# M161C.net
KiCad netlist of a schematic drawn in EAGLE
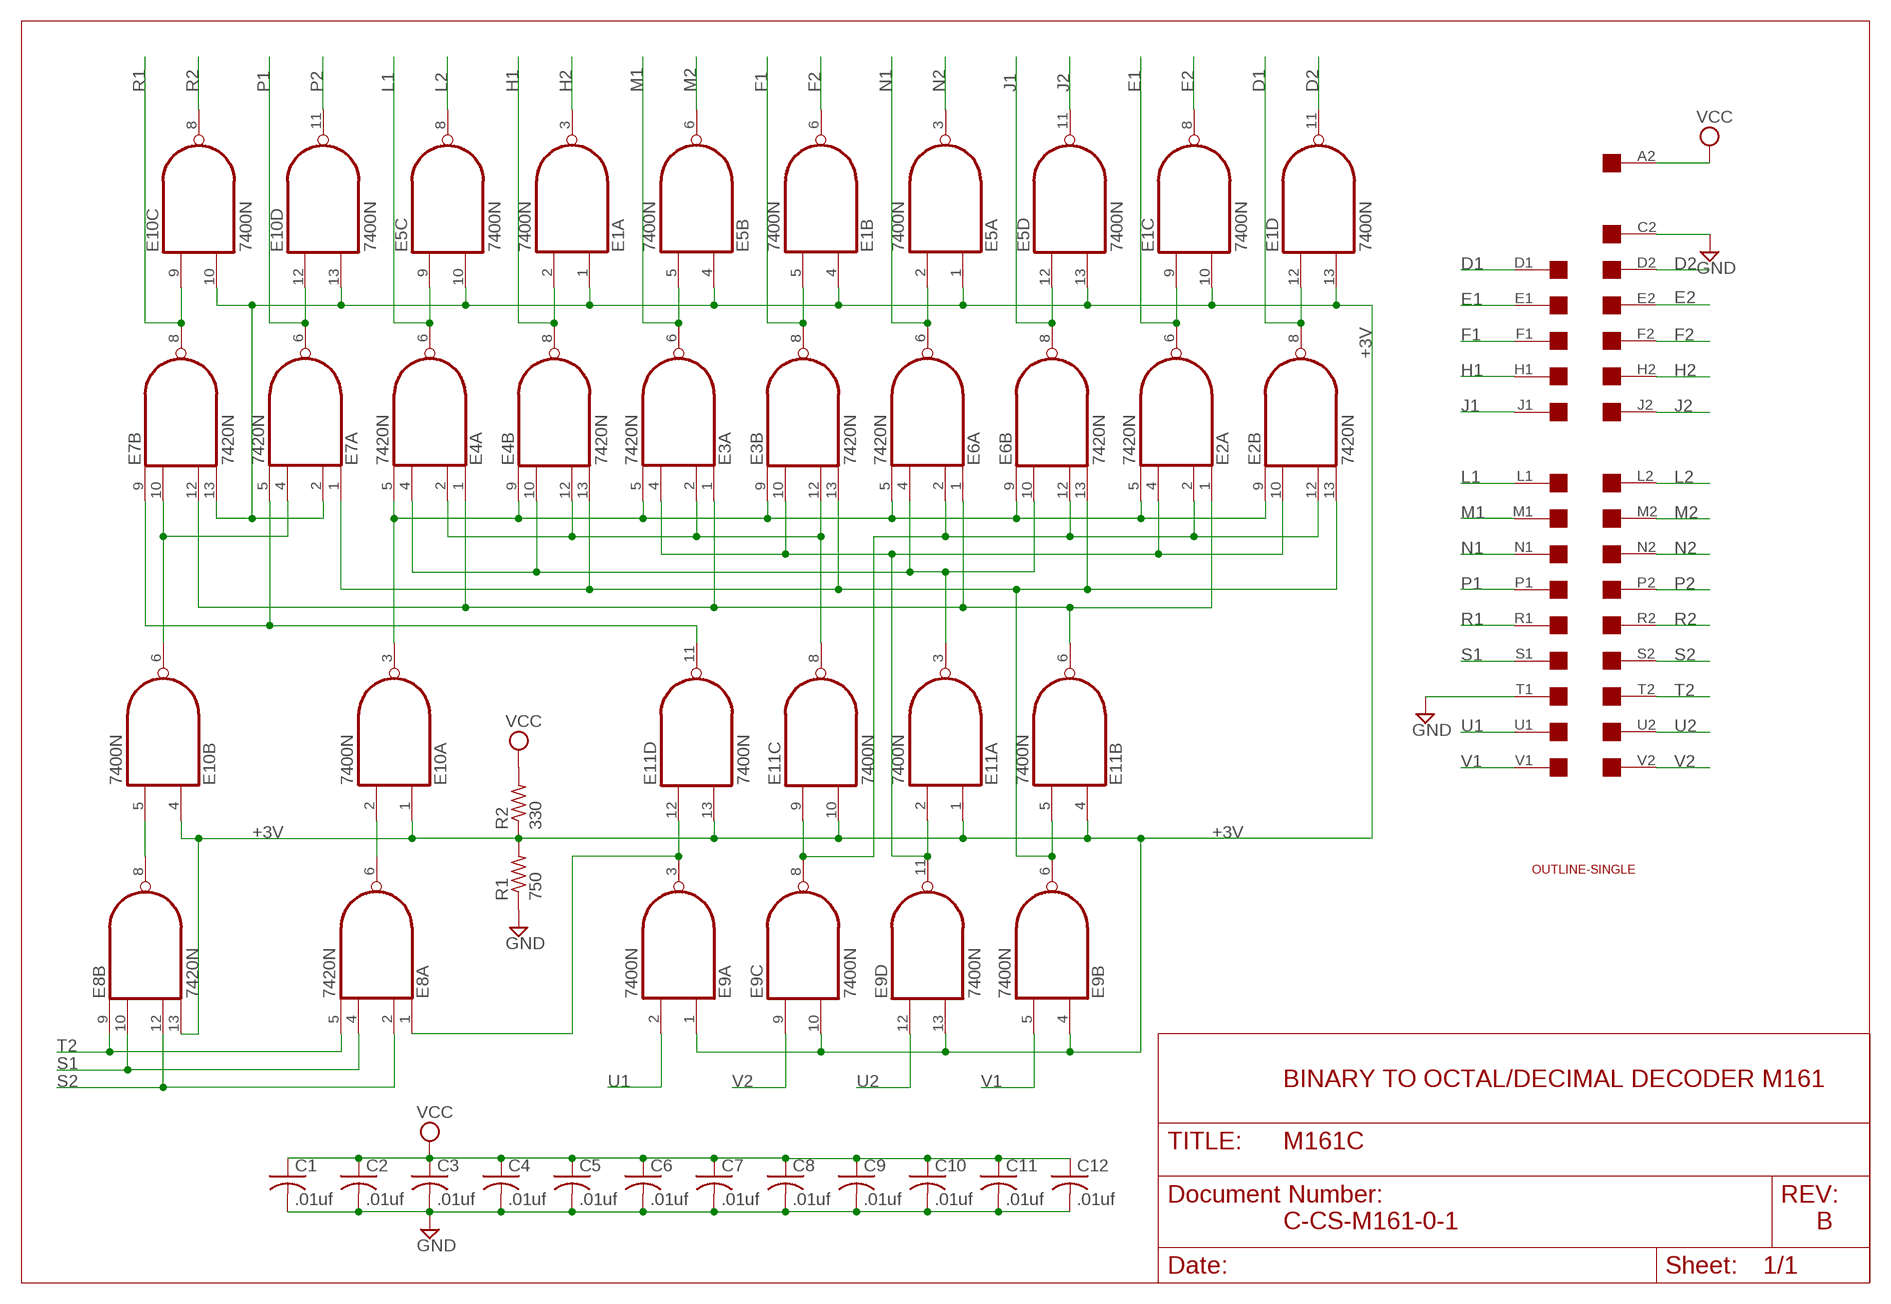
[diagram p0: schematic, sheet 1]

(export (version "E")
  (design (tool "Eeschema 10.0.6"))
  (components
    (comp (ref "C1")
      (value ".01uf")
      (footprint "eagle-import:C050-025X075")
      (libsource (lib "eagle-import") (part "C-US050-025X075"))
    )
    (comp (ref "C2")
      (value ".01uf")
      (footprint "eagle-import:C050-025X075")
      (libsource (lib "eagle-import") (part "C-US050-025X075"))
    )
    (comp (ref "C3")
      (value ".01uf")
      (footprint "eagle-import:C050-025X075")
      (libsource (lib "eagle-import") (part "C-US050-025X075"))
    )
    (comp (ref "C4")
      (value ".01uf")
      (footprint "eagle-import:C050-025X075")
      (libsource (lib "eagle-import") (part "C-US050-025X075"))
    )
    (comp (ref "C5")
      (value ".01uf")
      (footprint "eagle-import:C050-025X075")
      (libsource (lib "eagle-import") (part "C-US050-025X075"))
    )
    (comp (ref "C6")
      (value ".01uf")
      (footprint "eagle-import:C050-025X075")
      (libsource (lib "eagle-import") (part "C-US050-025X075"))
    )
    (comp (ref "C7")
      (value ".01uf")
      (footprint "eagle-import:C050-025X075")
      (libsource (lib "eagle-import") (part "C-US050-025X075"))
    )
    (comp (ref "C8")
      (value ".01uf")
      (footprint "eagle-import:C050-025X075")
      (libsource (lib "eagle-import") (part "C-US050-025X075"))
    )
    (comp (ref "C9")
      (value ".01uf")
      (footprint "eagle-import:C050-025X075")
      (libsource (lib "eagle-import") (part "C-US050-025X075"))
    )
    (comp (ref "C10")
      (value ".01uf")
      (footprint "eagle-import:C050-025X075")
      (libsource (lib "eagle-import") (part "C-US050-025X075"))
    )
    (comp (ref "C11")
      (value ".01uf")
      (footprint "eagle-import:C050-025X075")
      (libsource (lib "eagle-import") (part "C-US050-025X075"))
    )
    (comp (ref "C12")
      (value ".01uf")
      (footprint "eagle-import:C050-025X075")
      (libsource (lib "eagle-import") (part "C-US050-025X075"))
    )
    (comp (ref "E1")
      (value "7400N")
      (footprint "eagle-import:DIL14")
      (libsource (lib "eagle-import") (part "7400N"))
    )
    (comp (ref "E2")
      (value "7420N")
      (footprint "eagle-import:DIL14")
      (libsource (lib "eagle-import") (part "7420NS"))
    )
    (comp (ref "E3")
      (value "7420N")
      (footprint "eagle-import:DIL14")
      (libsource (lib "eagle-import") (part "7420NS"))
    )
    (comp (ref "E4")
      (value "7420N")
      (footprint "eagle-import:DIL14")
      (libsource (lib "eagle-import") (part "7420NS"))
    )
    (comp (ref "E5")
      (value "7400N")
      (footprint "eagle-import:DIL14")
      (libsource (lib "eagle-import") (part "7400N"))
    )
    (comp (ref "E6")
      (value "7420N")
      (footprint "eagle-import:DIL14")
      (libsource (lib "eagle-import") (part "7420NS"))
    )
    (comp (ref "E7")
      (value "7420N")
      (footprint "eagle-import:DIL14")
      (libsource (lib "eagle-import") (part "7420NS"))
    )
    (comp (ref "E8")
      (value "7420N")
      (footprint "eagle-import:DIL14")
      (libsource (lib "eagle-import") (part "7420NS"))
    )
    (comp (ref "E9")
      (value "7400N")
      (footprint "eagle-import:DIL14")
      (libsource (lib "eagle-import") (part "7400N"))
    )
    (comp (ref "E10")
      (value "7400N")
      (footprint "eagle-import:DIL14")
      (libsource (lib "eagle-import") (part "7400N"))
    )
    (comp (ref "E11")
      (value "7400N")
      (footprint "eagle-import:DIL14")
      (libsource (lib "eagle-import") (part "7400N"))
    )
    (comp (ref "R1")
      (value "750")
      (footprint "eagle-import:0207_10")
      (libsource (lib "eagle-import") (part "R-US_0207/10"))
    )
    (comp (ref "R2")
      (value "330")
      (footprint "eagle-import:0207_10")
      (libsource (lib "eagle-import") (part "R-US_0207/10"))
    )
    (comp (ref "U$1")
      (value "OUTLINE-SINGLE")
      (footprint "eagle-import:SINGLE")
      (libsource (lib "eagle-import") (part "OUTLINE-SINGLE"))
    )
    (comp (ref "U$4")
      (value "SINGLE")
      (footprint "eagle-import:EDGE-CON2")
      (libsource (lib "eagle-import") (part "SINGLE"))
    )
  )
  (nets
    (net (code "1") (name "/+3V") (class "Default")
      (node (ref "E1") (pin "1") (pinfunction "I0_1") (pintype "input"))
      (node (ref "E1") (pin "10") (pinfunction "I1_10") (pintype "input"))
      (node (ref "E1") (pin "13") (pinfunction "I1_13") (pintype "input"))
      (node (ref "E1") (pin "4") (pinfunction "I0_4") (pintype "input"))
      (node (ref "E10") (pin "1") (pinfunction "I0_1") (pintype "input"))
      (node (ref "E10") (pin "10") (pinfunction "I1_10") (pintype "input"))
      (node (ref "E10") (pin "13") (pinfunction "I1_13") (pintype "input"))
      (node (ref "E10") (pin "4") (pinfunction "I0_4") (pintype "input"))
      (node (ref "E11") (pin "1") (pinfunction "I0_1") (pintype "input"))
      (node (ref "E11") (pin "10") (pinfunction "I1_10") (pintype "input"))
      (node (ref "E11") (pin "13") (pinfunction "I1_13") (pintype "input"))
      (node (ref "E11") (pin "4") (pinfunction "I0_4") (pintype "input"))
      (node (ref "E5") (pin "1") (pinfunction "I0_1") (pintype "input"))
      (node (ref "E5") (pin "10") (pinfunction "I1_10") (pintype "input"))
      (node (ref "E5") (pin "13") (pinfunction "I1_13") (pintype "input"))
      (node (ref "E5") (pin "4") (pinfunction "I0_4") (pintype "input"))
      (node (ref "E7") (pin "13") (pinfunction "I3_13") (pintype "input"))
      (node (ref "E7") (pin "2") (pinfunction "I1_2") (pintype "input"))
      (node (ref "E8") (pin "13") (pinfunction "I3_13") (pintype "input"))
      (node (ref "E9") (pin "1") (pinfunction "I0_1") (pintype "input"))
      (node (ref "E9") (pin "10") (pinfunction "I1_10") (pintype "input"))
      (node (ref "E9") (pin "13") (pinfunction "I1_13") (pintype "input"))
      (node (ref "E9") (pin "4") (pinfunction "I0_4") (pintype "input"))
      (node (ref "R1") (pin "2") (pinfunction "2_2") (pintype "passive"))
      (node (ref "R2") (pin "1") (pinfunction "1_1") (pintype "passive"))
    )
    (net (code "2") (name "/D1") (class "Default")
      (node (ref "E1") (pin "12") (pinfunction "I0_12") (pintype "input"))
      (node (ref "E2") (pin "8") (pinfunction "O_8") (pintype "output"))
      (node (ref "U$4") (pin "D1") (pinfunction "1_D1") (pintype "bidirectional"))
    )
    (net (code "3") (name "/D2") (class "Default")
      (node (ref "E1") (pin "11") (pinfunction "O_11") (pintype "output"))
      (node (ref "U$4") (pin "D2") (pinfunction "1_D2") (pintype "bidirectional"))
    )
    (net (code "4") (name "/E1") (class "Default")
      (node (ref "E1") (pin "9") (pinfunction "I0_9") (pintype "input"))
      (node (ref "E2") (pin "6") (pinfunction "O_6") (pintype "output"))
      (node (ref "U$4") (pin "E1") (pinfunction "1_E1") (pintype "bidirectional"))
    )
    (net (code "5") (name "/E2") (class "Default")
      (node (ref "E1") (pin "8") (pinfunction "O_8") (pintype "output"))
      (node (ref "U$4") (pin "E2") (pinfunction "1_E2") (pintype "bidirectional"))
    )
    (net (code "6") (name "/F1") (class "Default")
      (node (ref "E1") (pin "5") (pinfunction "I1_5") (pintype "input"))
      (node (ref "E3") (pin "8") (pinfunction "O_8") (pintype "output"))
      (node (ref "U$4") (pin "F1") (pinfunction "1_F1") (pintype "bidirectional"))
    )
    (net (code "7") (name "/F2") (class "Default")
      (node (ref "E1") (pin "6") (pinfunction "O_6") (pintype "output"))
      (node (ref "U$4") (pin "F2") (pinfunction "1_F2") (pintype "bidirectional"))
    )
    (net (code "8") (name "/H1") (class "Default")
      (node (ref "E1") (pin "2") (pinfunction "I1_2") (pintype "input"))
      (node (ref "E4") (pin "8") (pinfunction "O_8") (pintype "output"))
      (node (ref "U$4") (pin "H1") (pinfunction "1_H1") (pintype "bidirectional"))
    )
    (net (code "9") (name "/H2") (class "Default")
      (node (ref "E1") (pin "3") (pinfunction "O_3") (pintype "output"))
      (node (ref "U$4") (pin "H2") (pinfunction "1_H2") (pintype "bidirectional"))
    )
    (net (code "10") (name "/J1") (class "Default")
      (node (ref "E5") (pin "12") (pinfunction "I0_12") (pintype "input"))
      (node (ref "E6") (pin "8") (pinfunction "O_8") (pintype "output"))
      (node (ref "U$4") (pin "J1") (pinfunction "1_J1") (pintype "bidirectional"))
    )
    (net (code "11") (name "/J2") (class "Default")
      (node (ref "E5") (pin "11") (pinfunction "O_11") (pintype "output"))
      (node (ref "U$4") (pin "J2") (pinfunction "1_J2") (pintype "bidirectional"))
    )
    (net (code "12") (name "/L1") (class "Default")
      (node (ref "E4") (pin "6") (pinfunction "O_6") (pintype "output"))
      (node (ref "E5") (pin "9") (pinfunction "I0_9") (pintype "input"))
      (node (ref "U$4") (pin "L1") (pinfunction "1_L1") (pintype "bidirectional"))
    )
    (net (code "13") (name "/L2") (class "Default")
      (node (ref "E5") (pin "8") (pinfunction "O_8") (pintype "output"))
      (node (ref "U$4") (pin "L2") (pinfunction "1_L2") (pintype "bidirectional"))
    )
    (net (code "14") (name "/M1") (class "Default")
      (node (ref "E3") (pin "6") (pinfunction "O_6") (pintype "output"))
      (node (ref "E5") (pin "5") (pinfunction "I1_5") (pintype "input"))
      (node (ref "U$4") (pin "M1") (pinfunction "1_M1") (pintype "bidirectional"))
    )
    (net (code "15") (name "/M2") (class "Default")
      (node (ref "E5") (pin "6") (pinfunction "O_6") (pintype "output"))
      (node (ref "U$4") (pin "M2") (pinfunction "1_M2") (pintype "bidirectional"))
    )
    (net (code "16") (name "/N1") (class "Default")
      (node (ref "E5") (pin "2") (pinfunction "I1_2") (pintype "input"))
      (node (ref "E6") (pin "6") (pinfunction "O_6") (pintype "output"))
      (node (ref "U$4") (pin "N1") (pinfunction "1_N1") (pintype "bidirectional"))
    )
    (net (code "17") (name "/N2") (class "Default")
      (node (ref "E5") (pin "3") (pinfunction "O_3") (pintype "output"))
      (node (ref "U$4") (pin "N2") (pinfunction "1_N2") (pintype "bidirectional"))
    )
    (net (code "18") (name "/P1") (class "Default")
      (node (ref "E10") (pin "12") (pinfunction "I0_12") (pintype "input"))
      (node (ref "E7") (pin "6") (pinfunction "O_6") (pintype "output"))
      (node (ref "U$4") (pin "P1") (pinfunction "1_P1") (pintype "bidirectional"))
    )
    (net (code "19") (name "/P2") (class "Default")
      (node (ref "E10") (pin "11") (pinfunction "O_11") (pintype "output"))
      (node (ref "U$4") (pin "P2") (pinfunction "1_P2") (pintype "bidirectional"))
    )
    (net (code "20") (name "/R1") (class "Default")
      (node (ref "E10") (pin "9") (pinfunction "I0_9") (pintype "input"))
      (node (ref "E7") (pin "8") (pinfunction "O_8") (pintype "output"))
      (node (ref "U$4") (pin "R1") (pinfunction "1_R1") (pintype "bidirectional"))
    )
    (net (code "21") (name "/R2") (class "Default")
      (node (ref "E10") (pin "8") (pinfunction "O_8") (pintype "output"))
      (node (ref "U$4") (pin "R2") (pinfunction "1_R2") (pintype "bidirectional"))
    )
    (net (code "22") (name "/S1") (class "Default")
      (node (ref "E8") (pin "10") (pinfunction "I1_10") (pintype "input"))
      (node (ref "E8") (pin "4") (pinfunction "I2_4") (pintype "input"))
      (node (ref "U$4") (pin "S1") (pinfunction "1_S1") (pintype "bidirectional"))
    )
    (net (code "23") (name "/S2") (class "Default")
      (node (ref "E8") (pin "12") (pinfunction "I2_12") (pintype "input"))
      (node (ref "E8") (pin "2") (pinfunction "I1_2") (pintype "input"))
      (node (ref "U$4") (pin "S2") (pinfunction "1_S2") (pintype "bidirectional"))
    )
    (net (code "24") (name "/T2") (class "Default")
      (node (ref "E8") (pin "5") (pinfunction "I3_5") (pintype "input"))
      (node (ref "E8") (pin "9") (pinfunction "I0_9") (pintype "input"))
      (node (ref "U$4") (pin "T2") (pinfunction "1_T2") (pintype "bidirectional"))
    )
    (net (code "25") (name "/U1") (class "Default")
      (node (ref "E9") (pin "2") (pinfunction "I1_2") (pintype "input"))
      (node (ref "U$4") (pin "U1") (pinfunction "1_U1") (pintype "bidirectional"))
    )
    (net (code "26") (name "/U2") (class "Default")
      (node (ref "E9") (pin "12") (pinfunction "I0_12") (pintype "input"))
      (node (ref "U$4") (pin "U2") (pinfunction "1_U2") (pintype "bidirectional"))
    )
    (net (code "27") (name "/V1") (class "Default")
      (node (ref "E9") (pin "5") (pinfunction "I1_5") (pintype "input"))
      (node (ref "U$4") (pin "V1") (pinfunction "1_V1") (pintype "bidirectional"))
    )
    (net (code "28") (name "/V2") (class "Default")
      (node (ref "E9") (pin "9") (pinfunction "I0_9") (pintype "input"))
      (node (ref "U$4") (pin "V2") (pinfunction "1_V2") (pintype "bidirectional"))
    )
    (net (code "29") (name "GND") (class "Default")
      (node (ref "C1") (pin "2") (pinfunction "2_2") (pintype "passive"))
      (node (ref "C10") (pin "2") (pinfunction "2_2") (pintype "passive"))
      (node (ref "C11") (pin "2") (pinfunction "2_2") (pintype "passive"))
      (node (ref "C12") (pin "2") (pinfunction "2_2") (pintype "passive"))
      (node (ref "C2") (pin "2") (pinfunction "2_2") (pintype "passive"))
      (node (ref "C3") (pin "2") (pinfunction "2_2") (pintype "passive"))
      (node (ref "C4") (pin "2") (pinfunction "2_2") (pintype "passive"))
      (node (ref "C5") (pin "2") (pinfunction "2_2") (pintype "passive"))
      (node (ref "C6") (pin "2") (pinfunction "2_2") (pintype "passive"))
      (node (ref "C7") (pin "2") (pinfunction "2_2") (pintype "passive"))
      (node (ref "C8") (pin "2") (pinfunction "2_2") (pintype "passive"))
      (node (ref "C9") (pin "2") (pinfunction "2_2") (pintype "passive"))
      (node (ref "R1") (pin "1") (pinfunction "1_1") (pintype "passive"))
      (node (ref "U$4") (pin "C2") (pinfunction "1_C2") (pintype "bidirectional"))
      (node (ref "U$4") (pin "T1") (pinfunction "1_T1") (pintype "bidirectional"))
    )
    (net (code "30") (name "Net-(E10A-I1)") (class "Default")
      (node (ref "E10") (pin "2") (pinfunction "I1_2") (pintype "input"))
      (node (ref "E8") (pin "6") (pinfunction "O_6") (pintype "output"))
    )
    (net (code "31") (name "Net-(E10A-O)") (class "Default")
      (node (ref "E10") (pin "3") (pinfunction "O_3") (pintype "output"))
      (node (ref "E2") (pin "5") (pinfunction "I3_5") (pintype "input"))
      (node (ref "E2") (pin "9") (pinfunction "I0_9") (pintype "input"))
      (node (ref "E3") (pin "5") (pinfunction "I3_5") (pintype "input"))
      (node (ref "E3") (pin "9") (pinfunction "I0_9") (pintype "input"))
      (node (ref "E4") (pin "5") (pinfunction "I3_5") (pintype "input"))
      (node (ref "E4") (pin "9") (pinfunction "I0_9") (pintype "input"))
      (node (ref "E6") (pin "5") (pinfunction "I3_5") (pintype "input"))
      (node (ref "E6") (pin "9") (pinfunction "I0_9") (pintype "input"))
    )
    (net (code "32") (name "Net-(E10B-I1)") (class "Default")
      (node (ref "E10") (pin "5") (pinfunction "I1_5") (pintype "input"))
      (node (ref "E8") (pin "8") (pinfunction "O_8") (pintype "output"))
    )
    (net (code "33") (name "Net-(E10B-O)") (class "Default")
      (node (ref "E10") (pin "6") (pinfunction "O_6") (pintype "output"))
      (node (ref "E7") (pin "10") (pinfunction "I1_10") (pintype "input"))
      (node (ref "E7") (pin "4") (pinfunction "I2_4") (pintype "input"))
    )
    (net (code "34") (name "Net-(E11A-I1)") (class "Default")
      (node (ref "E11") (pin "2") (pinfunction "I1_2") (pintype "input"))
      (node (ref "E2") (pin "10") (pinfunction "I1_10") (pintype "input"))
      (node (ref "E2") (pin "4") (pinfunction "I2_4") (pintype "input"))
      (node (ref "E3") (pin "10") (pinfunction "I1_10") (pintype "input"))
      (node (ref "E3") (pin "4") (pinfunction "I2_4") (pintype "input"))
      (node (ref "E9") (pin "11") (pinfunction "O_11") (pintype "output"))
    )
    (net (code "35") (name "Net-(E11A-O)") (class "Default")
      (node (ref "E11") (pin "3") (pinfunction "O_3") (pintype "output"))
      (node (ref "E4") (pin "10") (pinfunction "I1_10") (pintype "input"))
      (node (ref "E4") (pin "4") (pinfunction "I2_4") (pintype "input"))
      (node (ref "E6") (pin "10") (pinfunction "I1_10") (pintype "input"))
      (node (ref "E6") (pin "4") (pinfunction "I2_4") (pintype "input"))
    )
    (net (code "36") (name "Net-(E11B-I1)") (class "Default")
      (node (ref "E11") (pin "5") (pinfunction "I1_5") (pintype "input"))
      (node (ref "E2") (pin "13") (pinfunction "I3_13") (pintype "input"))
      (node (ref "E3") (pin "13") (pinfunction "I3_13") (pintype "input"))
      (node (ref "E4") (pin "13") (pinfunction "I3_13") (pintype "input"))
      (node (ref "E6") (pin "13") (pinfunction "I3_13") (pintype "input"))
      (node (ref "E7") (pin "1") (pinfunction "I0_1") (pintype "input"))
      (node (ref "E9") (pin "6") (pinfunction "O_6") (pintype "output"))
    )
    (net (code "37") (name "Net-(E11B-O)") (class "Default")
      (node (ref "E11") (pin "6") (pinfunction "O_6") (pintype "output"))
      (node (ref "E2") (pin "1") (pinfunction "I0_1") (pintype "input"))
      (node (ref "E3") (pin "1") (pinfunction "I0_1") (pintype "input"))
      (node (ref "E4") (pin "1") (pinfunction "I0_1") (pintype "input"))
      (node (ref "E6") (pin "1") (pinfunction "I0_1") (pintype "input"))
      (node (ref "E7") (pin "12") (pinfunction "I2_12") (pintype "input"))
    )
    (net (code "38") (name "Net-(E11C-I0)") (class "Default")
      (node (ref "E11") (pin "9") (pinfunction "I0_9") (pintype "input"))
      (node (ref "E2") (pin "12") (pinfunction "I2_12") (pintype "input"))
      (node (ref "E2") (pin "2") (pinfunction "I1_2") (pintype "input"))
      (node (ref "E6") (pin "12") (pinfunction "I2_12") (pintype "input"))
      (node (ref "E6") (pin "2") (pinfunction "I1_2") (pintype "input"))
      (node (ref "E9") (pin "8") (pinfunction "O_8") (pintype "output"))
    )
    (net (code "39") (name "Net-(E11C-O)") (class "Default")
      (node (ref "E11") (pin "8") (pinfunction "O_8") (pintype "output"))
      (node (ref "E3") (pin "12") (pinfunction "I2_12") (pintype "input"))
      (node (ref "E3") (pin "2") (pinfunction "I1_2") (pintype "input"))
      (node (ref "E4") (pin "12") (pinfunction "I2_12") (pintype "input"))
      (node (ref "E4") (pin "2") (pinfunction "I1_2") (pintype "input"))
    )
    (net (code "40") (name "Net-(E11D-I0)") (class "Default")
      (node (ref "E11") (pin "12") (pinfunction "I0_12") (pintype "input"))
      (node (ref "E8") (pin "1") (pinfunction "I0_1") (pintype "input"))
      (node (ref "E9") (pin "3") (pinfunction "O_3") (pintype "output"))
    )
    (net (code "41") (name "Net-(E11D-O)") (class "Default")
      (node (ref "E11") (pin "11") (pinfunction "O_11") (pintype "output"))
      (node (ref "E7") (pin "5") (pinfunction "I3_5") (pintype "input"))
      (node (ref "E7") (pin "9") (pinfunction "I0_9") (pintype "input"))
    )
    (net (code "42") (name "VCC") (class "Default")
      (node (ref "C1") (pin "1") (pinfunction "1_1") (pintype "passive"))
      (node (ref "C10") (pin "1") (pinfunction "1_1") (pintype "passive"))
      (node (ref "C11") (pin "1") (pinfunction "1_1") (pintype "passive"))
      (node (ref "C12") (pin "1") (pinfunction "1_1") (pintype "passive"))
      (node (ref "C2") (pin "1") (pinfunction "1_1") (pintype "passive"))
      (node (ref "C3") (pin "1") (pinfunction "1_1") (pintype "passive"))
      (node (ref "C4") (pin "1") (pinfunction "1_1") (pintype "passive"))
      (node (ref "C5") (pin "1") (pinfunction "1_1") (pintype "passive"))
      (node (ref "C6") (pin "1") (pinfunction "1_1") (pintype "passive"))
      (node (ref "C7") (pin "1") (pinfunction "1_1") (pintype "passive"))
      (node (ref "C8") (pin "1") (pinfunction "1_1") (pintype "passive"))
      (node (ref "C9") (pin "1") (pinfunction "1_1") (pintype "passive"))
      (node (ref "R2") (pin "2") (pinfunction "2_2") (pintype "passive"))
      (node (ref "U$4") (pin "A2") (pinfunction "1_A2") (pintype "bidirectional"))
    )
  )
)
